# KlokWave_Wave.net
KiCad netlist of a schematic drawn in Altium Designer
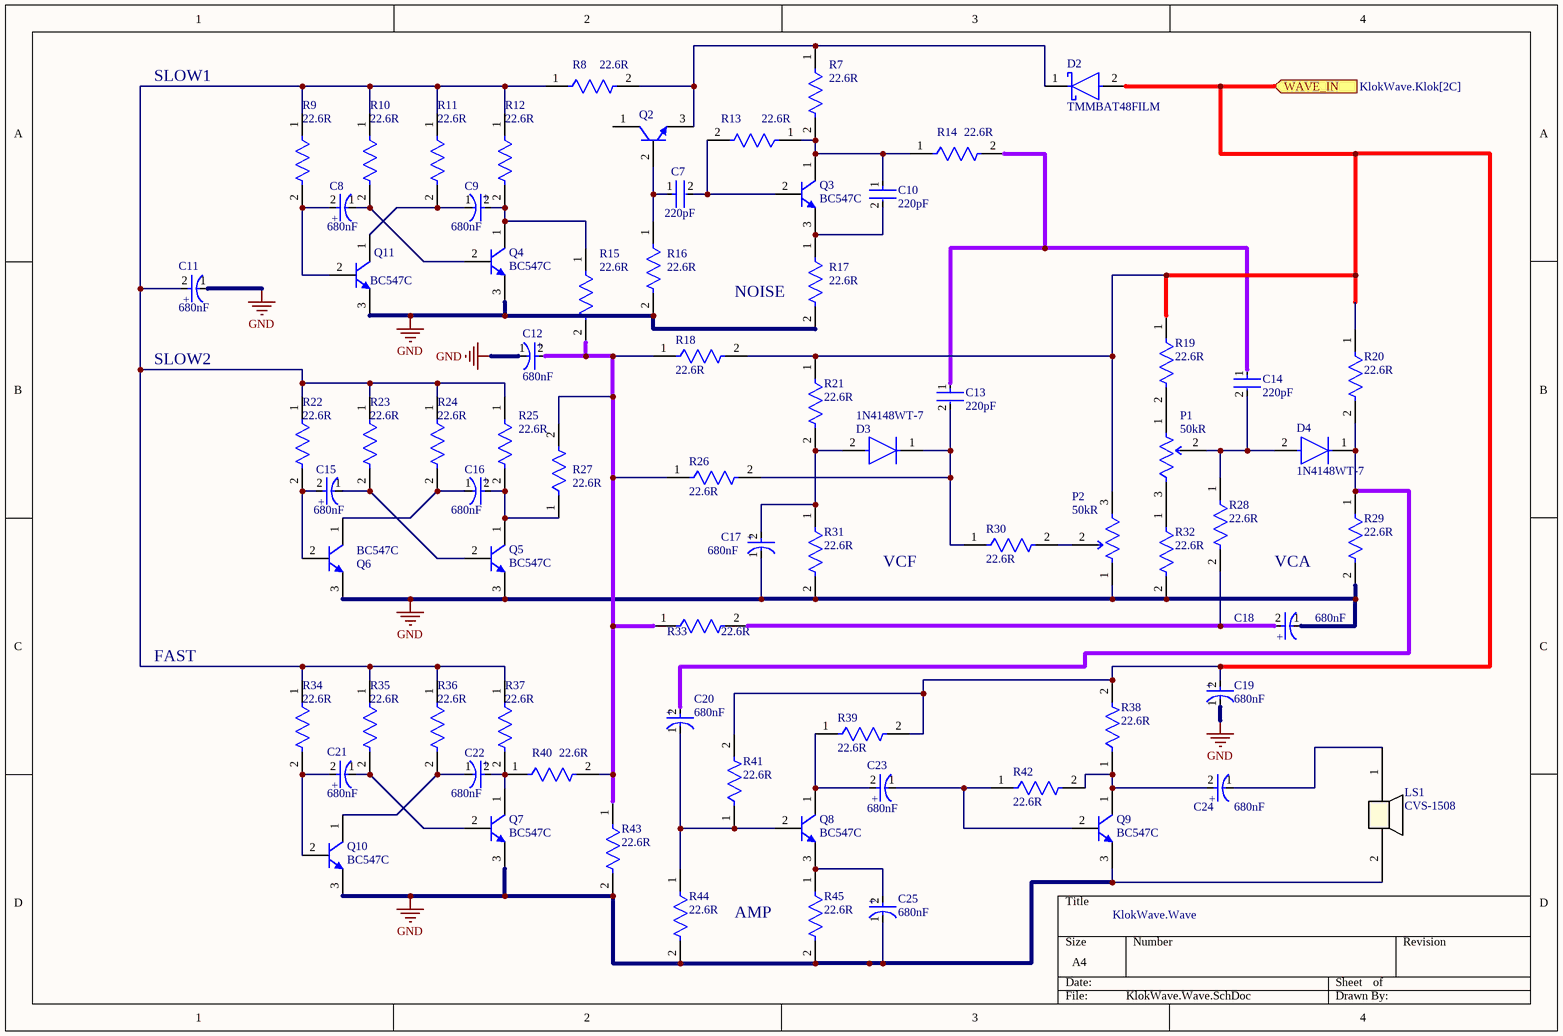
[diagram p0: KlokWave.Wave.SchDoc]

(export (version "E")
  (design (tool "Eeschema 10.0.6"))
  (components
    (comp (ref "C7")
      (value "CL21C221FBANNNC")
      (footprint "SMD RES: 0805ph")
      (description "SMD cap nonpol: CL21 Series 0805 220pF 50V ±1% Tolerance C0G Multilayer Ceramic Chip Capacitor")
      (fields (field (name "TOLERANCE") "1%") (field (name "CAPACITANCE") "220pF"))
      (libsource (lib "KlokWave") (part "CMP-13271-000769-1"))
    )
    (comp (ref "C8")
      (value "FP-OS-CON-SMT-C6-MFG")
      (footprint "SMD Elco pol: FP-OS-CON-SMT-C6-MFG")
      (description "SMD Elco Capacitor")
      (fields (field (name "CAPACITANCE") "680nF") (field (name "TOLERANCE") "10%"))
      (libsource (lib "KlokWave") (part "FP-OS-CON-SMT-C6-MFG"))
    )
    (comp (ref "C9")
      (value "FP-OS-CON-SMT-C6-MFG")
      (footprint "SMD Elco pol: FP-OS-CON-SMT-C6-MFG")
      (description "SMD Elco Capacitor")
      (fields (field (name "CAPACITANCE") "680nF") (field (name "TOLERANCE") "10%"))
      (libsource (lib "KlokWave") (part "FP-OS-CON-SMT-C6-MFG"))
    )
    (comp (ref "C10")
      (value "CL21C221FBANNNC")
      (footprint "SMD RES: 0805ph")
      (description "SMD cap nonpol: CL21 Series 0805 220pF 50V ±1% Tolerance C0G Multilayer Ceramic Chip Capacitor")
      (fields (field (name "TOLERANCE") "1%") (field (name "CAPACITANCE") "220pF"))
      (libsource (lib "KlokWave") (part "CMP-13271-000769-1"))
    )
    (comp (ref "C11")
      (value "FP-OS-CON-SMT-C6-MFG")
      (footprint "SMD Elco pol: FP-OS-CON-SMT-C6-MFG")
      (description "SMD Elco Capacitor")
      (fields (field (name "CAPACITANCE") "680nF") (field (name "TOLERANCE") "10%"))
      (libsource (lib "KlokWave") (part "FP-OS-CON-SMT-C6-MFG"))
    )
    (comp (ref "C12")
      (value "FP-OS-CON-SMT-C6-MFG")
      (footprint "SMD Elco pol: FP-OS-CON-SMT-C6-MFG")
      (description "SMD Elco Capacitor")
      (fields (field (name "CAPACITANCE") "680nF") (field (name "TOLERANCE") "10%"))
      (libsource (lib "KlokWave") (part "FP-OS-CON-SMT-C6-MFG"))
    )
    (comp (ref "C13")
      (value "CL21C221FBANNNC")
      (footprint "SMD RES: 0805ph")
      (description "SMD cap nonpol: CL21 Series 0805 220pF 50V ±1% Tolerance C0G Multilayer Ceramic Chip Capacitor")
      (fields (field (name "TOLERANCE") "1%") (field (name "CAPACITANCE") "220pF"))
      (libsource (lib "KlokWave") (part "CMP-13271-000769-1"))
    )
    (comp (ref "C14")
      (value "CL21C221FBANNNC")
      (footprint "SMD RES: 0805ph")
      (description "SMD cap nonpol: CL21 Series 0805 220pF 50V ±1% Tolerance C0G Multilayer Ceramic Chip Capacitor")
      (fields (field (name "TOLERANCE") "1%") (field (name "CAPACITANCE") "220pF"))
      (libsource (lib "KlokWave") (part "CMP-13271-000769-1"))
    )
    (comp (ref "C15")
      (value "FP-OS-CON-SMT-C6-MFG")
      (footprint "SMD Elco pol: FP-OS-CON-SMT-C6-MFG")
      (description "SMD Elco Capacitor")
      (fields (field (name "CAPACITANCE") "680nF") (field (name "TOLERANCE") "10%"))
      (libsource (lib "KlokWave") (part "FP-OS-CON-SMT-C6-MFG"))
    )
    (comp (ref "C16")
      (value "FP-OS-CON-SMT-C6-MFG")
      (footprint "SMD Elco pol: FP-OS-CON-SMT-C6-MFG")
      (description "SMD Elco Capacitor")
      (fields (field (name "CAPACITANCE") "680nF") (field (name "TOLERANCE") "10%"))
      (libsource (lib "KlokWave") (part "FP-OS-CON-SMT-C6-MFG"))
    )
    (comp (ref "C17")
      (value "FP-OS-CON-SMT-C6-MFG")
      (footprint "SMD Elco pol: FP-OS-CON-SMT-C6-MFG")
      (description "SMD Elco Capacitor")
      (fields (field (name "CAPACITANCE") "680nF") (field (name "TOLERANCE") "10%"))
      (libsource (lib "KlokWave") (part "FP-OS-CON-SMT-C6-MFG"))
    )
    (comp (ref "C18")
      (value "FP-OS-CON-SMT-C6-MFG")
      (footprint "SMD Elco pol: FP-OS-CON-SMT-C6-MFG")
      (description "SMD Elco Capacitor")
      (fields (field (name "CAPACITANCE") "680nF") (field (name "TOLERANCE") "10%"))
      (libsource (lib "KlokWave") (part "FP-OS-CON-SMT-C6-MFG"))
    )
    (comp (ref "C19")
      (value "FP-OS-CON-SMT-C6-MFG")
      (footprint "SMD Elco pol: FP-OS-CON-SMT-C6-MFG")
      (description "SMD Elco Capacitor")
      (fields (field (name "CAPACITANCE") "680nF") (field (name "TOLERANCE") "10%"))
      (libsource (lib "KlokWave") (part "FP-OS-CON-SMT-C6-MFG"))
    )
    (comp (ref "C20")
      (value "FP-OS-CON-SMT-C6-MFG")
      (footprint "SMD Elco pol: FP-OS-CON-SMT-C6-MFG")
      (description "SMD Elco Capacitor")
      (fields (field (name "CAPACITANCE") "680nF") (field (name "TOLERANCE") "10%"))
      (libsource (lib "KlokWave") (part "FP-OS-CON-SMT-C6-MFG"))
    )
    (comp (ref "C21")
      (value "FP-OS-CON-SMT-C6-MFG")
      (footprint "SMD Elco pol: FP-OS-CON-SMT-C6-MFG")
      (description "SMD Elco Capacitor")
      (fields (field (name "CAPACITANCE") "680nF") (field (name "TOLERANCE") "10%"))
      (libsource (lib "KlokWave") (part "FP-OS-CON-SMT-C6-MFG"))
    )
    (comp (ref "C22")
      (value "FP-OS-CON-SMT-C6-MFG")
      (footprint "SMD Elco pol: FP-OS-CON-SMT-C6-MFG")
      (description "SMD Elco Capacitor")
      (fields (field (name "CAPACITANCE") "680nF") (field (name "TOLERANCE") "10%"))
      (libsource (lib "KlokWave") (part "FP-OS-CON-SMT-C6-MFG"))
    )
    (comp (ref "C23")
      (value "FP-OS-CON-SMT-C6-MFG")
      (footprint "SMD Elco pol: FP-OS-CON-SMT-C6-MFG")
      (description "SMD Elco Capacitor")
      (fields (field (name "CAPACITANCE") "680nF") (field (name "TOLERANCE") "10%"))
      (libsource (lib "KlokWave") (part "FP-OS-CON-SMT-C6-MFG"))
    )
    (comp (ref "C24")
      (value "FP-OS-CON-SMT-C6-MFG")
      (footprint "SMD Elco pol: FP-OS-CON-SMT-C6-MFG")
      (description "SMD Elco Capacitor")
      (fields (field (name "CAPACITANCE") "680nF") (field (name "TOLERANCE") "10%"))
      (libsource (lib "KlokWave") (part "FP-OS-CON-SMT-C6-MFG"))
    )
    (comp (ref "C25")
      (value "FP-OS-CON-SMT-C6-MFG")
      (footprint "SMD Elco pol: FP-OS-CON-SMT-C6-MFG")
      (description "SMD Elco Capacitor")
      (fields (field (name "CAPACITANCE") "680nF") (field (name "TOLERANCE") "10%"))
      (libsource (lib "KlokWave") (part "FP-OS-CON-SMT-C6-MFG"))
    )
    (comp (ref "D2")
      (value "TMMBAT48FILM")
      (footprint "SMD Diode BAT48 FP-MINIMELF-MFG")
      (description "Rectifier Diode BAT48 SCHOTTKY 40V 350MA MINMELF")
      (fields
        (field (name "MANUFACTURER") "STMicroelectronics")
        (field (name "OCTOPART") "https://octopart.com/tmmbat48film-stmicroelectronics-324396")
      )
      (libsource (lib "KlokWave") (part "CMP-12187-000003-1"))
    )
    (comp (ref "D3")
      (value "1N4148WT-7")
      (footprint "SMD Diode Rect: FP-SOD523-MFG")
      (description "Rectifier Diode 1N4148 GEN PURP 80V 125MA SOD523")
      (libsource (lib "KlokWave") (part "CMP-2000-05518-3"))
    )
    (comp (ref "D4")
      (value "1N4148WT-7")
      (footprint "SMD Diode Rect: FP-SOD523-MFG")
      (description "Rectifier Diode 1N4148 GEN PURP 80V 125MA SOD523")
      (libsource (lib "KlokWave") (part "CMP-2000-05518-3"))
    )
    (comp (ref "LS1")
      (value "CVS-1508")
      (footprint "THT speaker: CVS-1508_CUD")
      (description "THT Speaker")
      (libsource (lib "KlokWave") (part "CVS-1508"))
    )
    (comp (ref "P1")
      (value "3361P-1-503GLF")
      (footprint "SMD POT: FP-3361P-MFG")
      (description "SMD TRIMMER 50K OHM 0.5W GW TOP ADJ")
      (fields (field (name "TOLERANCE") "10%") (field (name "RESISTANCE") "50kR"))
      (libsource (lib "KlokWave") (part "CMP-07234-000057-1"))
    )
    (comp (ref "P2")
      (value "3361P-1-503GLF")
      (footprint "SMD POT: FP-3361P-MFG")
      (description "SMD TRIMMER 50K OHM 0.5W GW TOP ADJ")
      (fields (field (name "TOLERANCE") "10%") (field (name "RESISTANCE") "50kR"))
      (libsource (lib "KlokWave") (part "CMP-07234-000057-1"))
    )
    (comp (ref "Q2")
      (value "BC547C")
      (footprint "THT NPN Transistor: ONSC-TO-92-3-29-11_AM_BL")
      (description "BC547C: THT Amplifier Transistor, NPN Silicon, 3-Pin TO-92, Bulk Box")
      (fields (field (name "MANUFACTURER") "On Semiconductor"))
      (libsource (lib "KlokWave") (part "CMP-1048-01437-1"))
    )
    (comp (ref "Q3")
      (value "BC547C")
      (footprint "THT NPN Transistor: ONSC-TO-92-3-29-11_AM_BL")
      (description "BC547C: THT Amplifier Transistor, NPN Silicon, 3-Pin TO-92, Bulk Box")
      (fields (field (name "MANUFACTURER") "On Semiconductor"))
      (libsource (lib "KlokWave") (part "CMP-1048-01437-1"))
    )
    (comp (ref "Q4")
      (value "BC547C")
      (footprint "THT NPN Transistor: ONSC-TO-92-3-29-11_AM_BL")
      (description "BC547C: THT Amplifier Transistor, NPN Silicon, 3-Pin TO-92, Bulk Box")
      (fields (field (name "MANUFACTURER") "On Semiconductor"))
      (libsource (lib "KlokWave") (part "CMP-1048-01437-1"))
    )
    (comp (ref "Q5")
      (value "BC547C")
      (footprint "THT NPN Transistor: ONSC-TO-92-3-29-11_AM_BL")
      (description "BC547C: THT Amplifier Transistor, NPN Silicon, 3-Pin TO-92, Bulk Box")
      (fields (field (name "MANUFACTURER") "On Semiconductor"))
      (libsource (lib "KlokWave") (part "CMP-1048-01437-1"))
    )
    (comp (ref "Q6")
      (value "BC547C")
      (footprint "THT NPN Transistor: ONSC-TO-92-3-29-11_AM_BL")
      (description "BC547C: THT Amplifier Transistor, NPN Silicon, 3-Pin TO-92, Bulk Box")
      (fields (field (name "MANUFACTURER") "On Semiconductor"))
      (libsource (lib "KlokWave") (part "CMP-1048-01437-1"))
    )
    (comp (ref "Q7")
      (value "BC547C")
      (footprint "THT NPN Transistor: ONSC-TO-92-3-29-11_AM_BL")
      (description "BC547C: THT Amplifier Transistor, NPN Silicon, 3-Pin TO-92, Bulk Box")
      (fields (field (name "MANUFACTURER") "On Semiconductor"))
      (libsource (lib "KlokWave") (part "CMP-1048-01437-1"))
    )
    (comp (ref "Q8")
      (value "BC547C")
      (footprint "THT NPN Transistor: ONSC-TO-92-3-29-11_AM_BL")
      (description "BC547C: THT Amplifier Transistor, NPN Silicon, 3-Pin TO-92, Bulk Box")
      (fields (field (name "MANUFACTURER") "On Semiconductor"))
      (libsource (lib "KlokWave") (part "CMP-1048-01437-1"))
    )
    (comp (ref "Q9")
      (value "BC547C")
      (footprint "THT NPN Transistor: ONSC-TO-92-3-29-11_AM_BL")
      (description "BC547C: THT Amplifier Transistor, NPN Silicon, 3-Pin TO-92, Bulk Box")
      (fields (field (name "MANUFACTURER") "On Semiconductor"))
      (libsource (lib "KlokWave") (part "CMP-1048-01437-1"))
    )
    (comp (ref "Q10")
      (value "BC547C")
      (footprint "THT NPN Transistor: ONSC-TO-92-3-29-11_AM_BL")
      (description "BC547C: THT Amplifier Transistor, NPN Silicon, 3-Pin TO-92, Bulk Box")
      (fields (field (name "MANUFACTURER") "On Semiconductor"))
      (libsource (lib "KlokWave") (part "CMP-1048-01437-1"))
    )
    (comp (ref "Q11")
      (value "BC547C")
      (footprint "THT NPN Transistor: ONSC-TO-92-3-29-11_AM_BL")
      (description "BC547C: THT Amplifier Transistor, NPN Silicon, 3-Pin TO-92, Bulk Box")
      (fields (field (name "MANUFACTURER") "On Semiconductor"))
      (libsource (lib "KlokWave") (part "CMP-1048-01437-1"))
    )
    (comp (ref "R7")
      (value "CR0805-FX-22R6ELF")
      (footprint "SMD RES: 0805ph")
      (description "Thick Film Chip Resistors 0805 22.6Ω 0.125W 1% 100ppm/°C")
      (fields (field (name "TOLERANCE") "1%") (field (name "RESISTANCE") "22.6R"))
      (libsource (lib "KlokWave") (part "CMP-07231-006076-1"))
    )
    (comp (ref "R8")
      (value "CR0805-FX-22R6ELF")
      (footprint "SMD RES: 0805ph")
      (description "Thick Film Chip Resistors 0805 22.6Ω 0.125W 1% 100ppm/°C")
      (fields (field (name "TOLERANCE") "1%") (field (name "RESISTANCE") "22.6R"))
      (libsource (lib "KlokWave") (part "CMP-07231-006076-1"))
    )
    (comp (ref "R9")
      (value "CR0805-FX-22R6ELF")
      (footprint "SMD RES: 0805ph")
      (description "Thick Film Chip Resistors 0805 22.6Ω 0.125W 1% 100ppm/°C")
      (fields (field (name "TOLERANCE") "1%") (field (name "RESISTANCE") "22.6R"))
      (libsource (lib "KlokWave") (part "CMP-07231-006076-1"))
    )
    (comp (ref "R10")
      (value "CR0805-FX-22R6ELF")
      (footprint "SMD RES: 0805ph")
      (description "Thick Film Chip Resistors 0805 22.6Ω 0.125W 1% 100ppm/°C")
      (fields (field (name "TOLERANCE") "1%") (field (name "RESISTANCE") "22.6R"))
      (libsource (lib "KlokWave") (part "CMP-07231-006076-1"))
    )
    (comp (ref "R11")
      (value "CR0805-FX-22R6ELF")
      (footprint "SMD RES: 0805ph")
      (description "Thick Film Chip Resistors 0805 22.6Ω 0.125W 1% 100ppm/°C")
      (fields (field (name "TOLERANCE") "1%") (field (name "RESISTANCE") "22.6R"))
      (libsource (lib "KlokWave") (part "CMP-07231-006076-1"))
    )
    (comp (ref "R12")
      (value "CR0805-FX-22R6ELF")
      (footprint "SMD RES: 0805ph")
      (description "Thick Film Chip Resistors 0805 22.6Ω 0.125W 1% 100ppm/°C")
      (fields (field (name "TOLERANCE") "1%") (field (name "RESISTANCE") "22.6R"))
      (libsource (lib "KlokWave") (part "CMP-07231-006076-1"))
    )
    (comp (ref "R13")
      (value "CR0805-FX-22R6ELF")
      (footprint "SMD RES: 0805ph")
      (description "Thick Film Chip Resistors 0805 22.6Ω 0.125W 1% 100ppm/°C")
      (fields (field (name "TOLERANCE") "1%") (field (name "RESISTANCE") "22.6R"))
      (libsource (lib "KlokWave") (part "CMP-07231-006076-1"))
    )
    (comp (ref "R14")
      (value "CR0805-FX-22R6ELF")
      (footprint "SMD RES: 0805ph")
      (description "Thick Film Chip Resistors 0805 22.6Ω 0.125W 1% 100ppm/°C")
      (fields (field (name "TOLERANCE") "1%") (field (name "RESISTANCE") "22.6R"))
      (libsource (lib "KlokWave") (part "CMP-07231-006076-1"))
    )
    (comp (ref "R15")
      (value "CR0805-FX-22R6ELF")
      (footprint "SMD RES: 0805ph")
      (description "Thick Film Chip Resistors 0805 22.6Ω 0.125W 1% 100ppm/°C")
      (fields (field (name "TOLERANCE") "1%") (field (name "RESISTANCE") "22.6R"))
      (libsource (lib "KlokWave") (part "CMP-07231-006076-1"))
    )
    (comp (ref "R16")
      (value "CR0805-FX-22R6ELF")
      (footprint "SMD RES: 0805ph")
      (description "Thick Film Chip Resistors 0805 22.6Ω 0.125W 1% 100ppm/°C")
      (fields (field (name "TOLERANCE") "1%") (field (name "RESISTANCE") "22.6R"))
      (libsource (lib "KlokWave") (part "CMP-07231-006076-1"))
    )
    (comp (ref "R17")
      (value "CR0805-FX-22R6ELF")
      (footprint "SMD RES: 0805ph")
      (description "Thick Film Chip Resistors 0805 22.6Ω 0.125W 1% 100ppm/°C")
      (fields (field (name "TOLERANCE") "1%") (field (name "RESISTANCE") "22.6R"))
      (libsource (lib "KlokWave") (part "CMP-07231-006076-1"))
    )
    (comp (ref "R18")
      (value "CR0805-FX-22R6ELF")
      (footprint "SMD RES: 0805ph")
      (description "Thick Film Chip Resistors 0805 22.6Ω 0.125W 1% 100ppm/°C")
      (fields (field (name "TOLERANCE") "1%") (field (name "RESISTANCE") "22.6R"))
      (libsource (lib "KlokWave") (part "CMP-07231-006076-1"))
    )
    (comp (ref "R19")
      (value "CR0805-FX-22R6ELF")
      (footprint "SMD RES: 0805ph")
      (description "Thick Film Chip Resistors 0805 22.6Ω 0.125W 1% 100ppm/°C")
      (fields (field (name "TOLERANCE") "1%") (field (name "RESISTANCE") "22.6R"))
      (libsource (lib "KlokWave") (part "CMP-07231-006076-1"))
    )
    (comp (ref "R20")
      (value "CR0805-FX-22R6ELF")
      (footprint "SMD RES: 0805ph")
      (description "Thick Film Chip Resistors 0805 22.6Ω 0.125W 1% 100ppm/°C")
      (fields (field (name "TOLERANCE") "1%") (field (name "RESISTANCE") "22.6R"))
      (libsource (lib "KlokWave") (part "CMP-07231-006076-1"))
    )
    (comp (ref "R21")
      (value "CR0805-FX-22R6ELF")
      (footprint "SMD RES: 0805ph")
      (description "Thick Film Chip Resistors 0805 22.6Ω 0.125W 1% 100ppm/°C")
      (fields (field (name "TOLERANCE") "1%") (field (name "RESISTANCE") "22.6R"))
      (libsource (lib "KlokWave") (part "CMP-07231-006076-1"))
    )
    (comp (ref "R22")
      (value "CR0805-FX-22R6ELF")
      (footprint "SMD RES: 0805ph")
      (description "Thick Film Chip Resistors 0805 22.6Ω 0.125W 1% 100ppm/°C")
      (fields (field (name "TOLERANCE") "1%") (field (name "RESISTANCE") "22.6R"))
      (libsource (lib "KlokWave") (part "CMP-07231-006076-1"))
    )
    (comp (ref "R23")
      (value "CR0805-FX-22R6ELF")
      (footprint "SMD RES: 0805ph")
      (description "Thick Film Chip Resistors 0805 22.6Ω 0.125W 1% 100ppm/°C")
      (fields (field (name "TOLERANCE") "1%") (field (name "RESISTANCE") "22.6R"))
      (libsource (lib "KlokWave") (part "CMP-07231-006076-1"))
    )
    (comp (ref "R24")
      (value "CR0805-FX-22R6ELF")
      (footprint "SMD RES: 0805ph")
      (description "Thick Film Chip Resistors 0805 22.6Ω 0.125W 1% 100ppm/°C")
      (fields (field (name "TOLERANCE") "1%") (field (name "RESISTANCE") "22.6R"))
      (libsource (lib "KlokWave") (part "CMP-07231-006076-1"))
    )
    (comp (ref "R25")
      (value "CR0805-FX-22R6ELF")
      (footprint "SMD RES: 0805ph")
      (description "Thick Film Chip Resistors 0805 22.6Ω 0.125W 1% 100ppm/°C")
      (fields (field (name "TOLERANCE") "1%") (field (name "RESISTANCE") "22.6R"))
      (libsource (lib "KlokWave") (part "CMP-07231-006076-1"))
    )
    (comp (ref "R26")
      (value "CR0805-FX-22R6ELF")
      (footprint "SMD RES: 0805ph")
      (description "Thick Film Chip Resistors 0805 22.6Ω 0.125W 1% 100ppm/°C")
      (fields (field (name "TOLERANCE") "1%") (field (name "RESISTANCE") "22.6R"))
      (libsource (lib "KlokWave") (part "CMP-07231-006076-1"))
    )
    (comp (ref "R27")
      (value "CR0805-FX-22R6ELF")
      (footprint "SMD RES: 0805ph")
      (description "Thick Film Chip Resistors 0805 22.6Ω 0.125W 1% 100ppm/°C")
      (fields (field (name "TOLERANCE") "1%") (field (name "RESISTANCE") "22.6R"))
      (libsource (lib "KlokWave") (part "CMP-07231-006076-1"))
    )
    (comp (ref "R28")
      (value "CR0805-FX-22R6ELF")
      (footprint "SMD RES: 0805ph")
      (description "Thick Film Chip Resistors 0805 22.6Ω 0.125W 1% 100ppm/°C")
      (fields (field (name "TOLERANCE") "1%") (field (name "RESISTANCE") "22.6R"))
      (libsource (lib "KlokWave") (part "CMP-07231-006076-1"))
    )
    (comp (ref "R29")
      (value "CR0805-FX-22R6ELF")
      (footprint "SMD RES: 0805ph")
      (description "Thick Film Chip Resistors 0805 22.6Ω 0.125W 1% 100ppm/°C")
      (fields (field (name "TOLERANCE") "1%") (field (name "RESISTANCE") "22.6R"))
      (libsource (lib "KlokWave") (part "CMP-07231-006076-1"))
    )
    (comp (ref "R30")
      (value "CR0805-FX-22R6ELF")
      (footprint "SMD RES: 0805ph")
      (description "Thick Film Chip Resistors 0805 22.6Ω 0.125W 1% 100ppm/°C")
      (fields (field (name "TOLERANCE") "1%") (field (name "RESISTANCE") "22.6R"))
      (libsource (lib "KlokWave") (part "CMP-07231-006076-1"))
    )
    (comp (ref "R31")
      (value "CR0805-FX-22R6ELF")
      (footprint "SMD RES: 0805ph")
      (description "Thick Film Chip Resistors 0805 22.6Ω 0.125W 1% 100ppm/°C")
      (fields (field (name "TOLERANCE") "1%") (field (name "RESISTANCE") "22.6R"))
      (libsource (lib "KlokWave") (part "CMP-07231-006076-1"))
    )
    (comp (ref "R32")
      (value "CR0805-FX-22R6ELF")
      (footprint "SMD RES: 0805ph")
      (description "Thick Film Chip Resistors 0805 22.6Ω 0.125W 1% 100ppm/°C")
      (fields (field (name "TOLERANCE") "1%") (field (name "RESISTANCE") "22.6R"))
      (libsource (lib "KlokWave") (part "CMP-07231-006076-1"))
    )
    (comp (ref "R33")
      (value "CR0805-FX-22R6ELF")
      (footprint "SMD RES: 0805ph")
      (description "Thick Film Chip Resistors 0805 22.6Ω 0.125W 1% 100ppm/°C")
      (fields (field (name "TOLERANCE") "1%") (field (name "RESISTANCE") "22.6R"))
      (libsource (lib "KlokWave") (part "CMP-07231-006076-1"))
    )
    (comp (ref "R34")
      (value "CR0805-FX-22R6ELF")
      (footprint "SMD RES: 0805ph")
      (description "Thick Film Chip Resistors 0805 22.6Ω 0.125W 1% 100ppm/°C")
      (fields (field (name "TOLERANCE") "1%") (field (name "RESISTANCE") "22.6R"))
      (libsource (lib "KlokWave") (part "CMP-07231-006076-1"))
    )
    (comp (ref "R35")
      (value "CR0805-FX-22R6ELF")
      (footprint "SMD RES: 0805ph")
      (description "Thick Film Chip Resistors 0805 22.6Ω 0.125W 1% 100ppm/°C")
      (fields (field (name "TOLERANCE") "1%") (field (name "RESISTANCE") "22.6R"))
      (libsource (lib "KlokWave") (part "CMP-07231-006076-1"))
    )
    (comp (ref "R36")
      (value "CR0805-FX-22R6ELF")
      (footprint "SMD RES: 0805ph")
      (description "Thick Film Chip Resistors 0805 22.6Ω 0.125W 1% 100ppm/°C")
      (fields (field (name "TOLERANCE") "1%") (field (name "RESISTANCE") "22.6R"))
      (libsource (lib "KlokWave") (part "CMP-07231-006076-1"))
    )
    (comp (ref "R37")
      (value "CR0805-FX-22R6ELF")
      (footprint "SMD RES: 0805ph")
      (description "Thick Film Chip Resistors 0805 22.6Ω 0.125W 1% 100ppm/°C")
      (fields (field (name "TOLERANCE") "1%") (field (name "RESISTANCE") "22.6R"))
      (libsource (lib "KlokWave") (part "CMP-07231-006076-1"))
    )
    (comp (ref "R38")
      (value "CR0805-FX-22R6ELF")
      (footprint "SMD RES: 0805ph")
      (description "Thick Film Chip Resistors 0805 22.6Ω 0.125W 1% 100ppm/°C")
      (fields (field (name "TOLERANCE") "1%") (field (name "RESISTANCE") "22.6R"))
      (libsource (lib "KlokWave") (part "CMP-07231-006076-1"))
    )
    (comp (ref "R39")
      (value "CR0805-FX-22R6ELF")
      (footprint "SMD RES: 0805ph")
      (description "Thick Film Chip Resistors 0805 22.6Ω 0.125W 1% 100ppm/°C")
      (fields (field (name "TOLERANCE") "1%") (field (name "RESISTANCE") "22.6R"))
      (libsource (lib "KlokWave") (part "CMP-07231-006076-1"))
    )
    (comp (ref "R40")
      (value "CR0805-FX-22R6ELF")
      (footprint "SMD RES: 0805ph")
      (description "Thick Film Chip Resistors 0805 22.6Ω 0.125W 1% 100ppm/°C")
      (fields (field (name "TOLERANCE") "1%") (field (name "RESISTANCE") "22.6R"))
      (libsource (lib "KlokWave") (part "CMP-07231-006076-1"))
    )
    (comp (ref "R41")
      (value "CR0805-FX-22R6ELF")
      (footprint "SMD RES: 0805ph")
      (description "Thick Film Chip Resistors 0805 22.6Ω 0.125W 1% 100ppm/°C")
      (fields (field (name "TOLERANCE") "1%") (field (name "RESISTANCE") "22.6R"))
      (libsource (lib "KlokWave") (part "CMP-07231-006076-1"))
    )
    (comp (ref "R42")
      (value "CR0805-FX-22R6ELF")
      (footprint "SMD RES: 0805ph")
      (description "Thick Film Chip Resistors 0805 22.6Ω 0.125W 1% 100ppm/°C")
      (fields (field (name "TOLERANCE") "1%") (field (name "RESISTANCE") "22.6R"))
      (libsource (lib "KlokWave") (part "CMP-07231-006076-1"))
    )
    (comp (ref "R43")
      (value "CR0805-FX-22R6ELF")
      (footprint "SMD RES: 0805ph")
      (description "Thick Film Chip Resistors 0805 22.6Ω 0.125W 1% 100ppm/°C")
      (fields (field (name "TOLERANCE") "1%") (field (name "RESISTANCE") "22.6R"))
      (libsource (lib "KlokWave") (part "CMP-07231-006076-1"))
    )
    (comp (ref "R44")
      (value "CR0805-FX-22R6ELF")
      (footprint "SMD RES: 0805ph")
      (description "Thick Film Chip Resistors 0805 22.6Ω 0.125W 1% 100ppm/°C")
      (fields (field (name "TOLERANCE") "1%") (field (name "RESISTANCE") "22.6R"))
      (libsource (lib "KlokWave") (part "CMP-07231-006076-1"))
    )
    (comp (ref "R45")
      (value "CR0805-FX-22R6ELF")
      (footprint "SMD RES: 0805ph")
      (description "Thick Film Chip Resistors 0805 22.6Ω 0.125W 1% 100ppm/°C")
      (fields (field (name "TOLERANCE") "1%") (field (name "RESISTANCE") "22.6R"))
      (libsource (lib "KlokWave") (part "CMP-07231-006076-1"))
    )
  )
  (nets
    (net (code "1") (name "/WAVE_IN") (class "Default")
      (node (ref "C19") (pin "2") (pinfunction "A_2") (pintype "passive"))
      (node (ref "D2") (pin "2") (pinfunction "A_2") (pintype "passive"))
      (node (ref "P2") (pin "3") (pinfunction "CW_3") (pintype "passive"))
      (node (ref "R18") (pin "2") (pinfunction "2_2") (pintype "passive"))
      (node (ref "R19") (pin "1") (pinfunction "1_1") (pintype "passive"))
      (node (ref "R20") (pin "1") (pinfunction "1_1") (pintype "passive"))
      (node (ref "R21") (pin "1") (pinfunction "1_1") (pintype "passive"))
      (node (ref "R38") (pin "2") (pinfunction "2_2") (pintype "passive"))
      (node (ref "R39") (pin "2") (pinfunction "2_2") (pintype "passive"))
      (node (ref "R41") (pin "2") (pinfunction "2_2") (pintype "passive"))
    )
    (net (code "2") (name "GND") (class "Default")
      (node (ref "C11") (pin "1") (pinfunction "C_1") (pintype "passive"))
      (node (ref "C12") (pin "1") (pinfunction "C_1") (pintype "passive"))
      (node (ref "C17") (pin "1") (pinfunction "C_1") (pintype "passive"))
      (node (ref "C18") (pin "1") (pinfunction "C_1") (pintype "passive"))
      (node (ref "C19") (pin "1") (pinfunction "C_1") (pintype "passive"))
      (node (ref "C25") (pin "1") (pinfunction "C_1") (pintype "passive"))
      (node (ref "LS1") (pin "2") (pinfunction "2_2") (pintype "passive"))
      (node (ref "P2") (pin "1") (pinfunction "CCW_1") (pintype "passive"))
      (node (ref "Q10") (pin "3") (pinfunction "E_3") (pintype "passive"))
      (node (ref "Q11") (pin "3") (pinfunction "E_3") (pintype "passive"))
      (node (ref "Q4") (pin "3") (pinfunction "E_3") (pintype "passive"))
      (node (ref "Q5") (pin "3") (pinfunction "E_3") (pintype "passive"))
      (node (ref "Q6") (pin "3") (pinfunction "E_3") (pintype "passive"))
      (node (ref "Q7") (pin "3") (pinfunction "E_3") (pintype "passive"))
      (node (ref "Q9") (pin "3") (pinfunction "E_3") (pintype "passive"))
      (node (ref "R16") (pin "2") (pinfunction "2_2") (pintype "passive"))
      (node (ref "R17") (pin "2") (pinfunction "2_2") (pintype "passive"))
      (node (ref "R29") (pin "2") (pinfunction "2_2") (pintype "passive"))
      (node (ref "R31") (pin "2") (pinfunction "2_2") (pintype "passive"))
      (node (ref "R32") (pin "2") (pinfunction "2_2") (pintype "passive"))
      (node (ref "R43") (pin "2") (pinfunction "2_2") (pintype "passive"))
      (node (ref "R44") (pin "2") (pinfunction "2_2") (pintype "passive"))
      (node (ref "R45") (pin "2") (pinfunction "2_2") (pintype "passive"))
    )
    (net (code "3") (name "Net-(C8-A)") (class "Default")
      (node (ref "C8") (pin "2") (pinfunction "A_2") (pintype "passive"))
      (node (ref "Q11") (pin "2") (pinfunction "B_2") (pintype "passive"))
      (node (ref "R9") (pin "2") (pinfunction "2_2") (pintype "passive"))
    )
    (net (code "4") (name "Net-(C8-C)") (class "Default")
      (node (ref "C8") (pin "1") (pinfunction "C_1") (pintype "passive"))
      (node (ref "Q4") (pin "2") (pinfunction "B_2") (pintype "passive"))
      (node (ref "R10") (pin "2") (pinfunction "2_2") (pintype "passive"))
    )
    (net (code "5") (name "Net-(C9-A)") (class "Default")
      (node (ref "C9") (pin "2") (pinfunction "A_2") (pintype "passive"))
      (node (ref "Q4") (pin "1") (pinfunction "C_1") (pintype "passive"))
      (node (ref "R12") (pin "2") (pinfunction "2_2") (pintype "passive"))
      (node (ref "R15") (pin "1") (pinfunction "1_1") (pintype "passive"))
    )
    (net (code "6") (name "Net-(C9-C)") (class "Default")
      (node (ref "C9") (pin "1") (pinfunction "C_1") (pintype "passive"))
      (node (ref "Q11") (pin "1") (pinfunction "C_1") (pintype "passive"))
      (node (ref "R11") (pin "2") (pinfunction "2_2") (pintype "passive"))
    )
    (net (code "7") (name "Net-(C11-A)") (class "Default")
      (node (ref "C11") (pin "2") (pinfunction "A_2") (pintype "passive"))
      (node (ref "R10") (pin "1") (pinfunction "1_1") (pintype "passive"))
      (node (ref "R11") (pin "1") (pinfunction "1_1") (pintype "passive"))
      (node (ref "R12") (pin "1") (pinfunction "1_1") (pintype "passive"))
      (node (ref "R22") (pin "1") (pinfunction "1_1") (pintype "passive"))
      (node (ref "R23") (pin "1") (pinfunction "1_1") (pintype "passive"))
      (node (ref "R24") (pin "1") (pinfunction "1_1") (pintype "passive"))
      (node (ref "R25") (pin "1") (pinfunction "1_1") (pintype "passive"))
      (node (ref "R34") (pin "1") (pinfunction "1_1") (pintype "passive"))
      (node (ref "R35") (pin "1") (pinfunction "1_1") (pintype "passive"))
      (node (ref "R36") (pin "1") (pinfunction "1_1") (pintype "passive"))
      (node (ref "R37") (pin "1") (pinfunction "1_1") (pintype "passive"))
      (node (ref "R8") (pin "1") (pinfunction "1_1") (pintype "passive"))
      (node (ref "R9") (pin "1") (pinfunction "1_1") (pintype "passive"))
    )
    (net (code "8") (name "Net-(C12-A)") (class "Default")
      (node (ref "C12") (pin "2") (pinfunction "A_2") (pintype "passive"))
      (node (ref "R15") (pin "2") (pinfunction "2_2") (pintype "passive"))
      (node (ref "R18") (pin "1") (pinfunction "1_1") (pintype "passive"))
      (node (ref "R26") (pin "1") (pinfunction "1_1") (pintype "passive"))
      (node (ref "R27") (pin "2") (pinfunction "2_2") (pintype "passive"))
      (node (ref "R33") (pin "1") (pinfunction "1_1") (pintype "passive"))
      (node (ref "R40") (pin "2") (pinfunction "2_2") (pintype "passive"))
      (node (ref "R43") (pin "1") (pinfunction "1_1") (pintype "passive"))
    )
    (net (code "9") (name "Net-(C13-Pad1)") (class "Default")
      (node (ref "C13") (pin "1") (pinfunction "1_1") (pintype "passive"))
      (node (ref "C14") (pin "1") (pinfunction "1_1") (pintype "passive"))
      (node (ref "R14") (pin "2") (pinfunction "2_2") (pintype "passive"))
    )
    (net (code "10") (name "Net-(C15-A)") (class "Default")
      (node (ref "C15") (pin "2") (pinfunction "A_2") (pintype "passive"))
      (node (ref "Q6") (pin "2") (pinfunction "B_2") (pintype "passive"))
      (node (ref "R22") (pin "2") (pinfunction "2_2") (pintype "passive"))
    )
    (net (code "11") (name "Net-(C15-C)") (class "Default")
      (node (ref "C15") (pin "1") (pinfunction "C_1") (pintype "passive"))
      (node (ref "Q5") (pin "2") (pinfunction "B_2") (pintype "passive"))
      (node (ref "R23") (pin "2") (pinfunction "2_2") (pintype "passive"))
    )
    (net (code "12") (name "Net-(C16-A)") (class "Default")
      (node (ref "C16") (pin "2") (pinfunction "A_2") (pintype "passive"))
      (node (ref "Q5") (pin "1") (pinfunction "C_1") (pintype "passive"))
      (node (ref "R25") (pin "2") (pinfunction "2_2") (pintype "passive"))
      (node (ref "R27") (pin "1") (pinfunction "1_1") (pintype "passive"))
    )
    (net (code "13") (name "Net-(C16-C)") (class "Default")
      (node (ref "C16") (pin "1") (pinfunction "C_1") (pintype "passive"))
      (node (ref "Q6") (pin "1") (pinfunction "C_1") (pintype "passive"))
      (node (ref "R24") (pin "2") (pinfunction "2_2") (pintype "passive"))
    )
    (net (code "14") (name "Net-(C17-A)") (class "Default")
      (node (ref "C17") (pin "2") (pinfunction "A_2") (pintype "passive"))
      (node (ref "D3") (pin "2") (pinfunction "A_2") (pintype "passive"))
      (node (ref "R21") (pin "2") (pinfunction "2_2") (pintype "passive"))
      (node (ref "R31") (pin "1") (pinfunction "1_1") (pintype "passive"))
    )
    (net (code "15") (name "Net-(C18-A)") (class "Default")
      (node (ref "C18") (pin "2") (pinfunction "A_2") (pintype "passive"))
      (node (ref "R28") (pin "2") (pinfunction "2_2") (pintype "passive"))
      (node (ref "R33") (pin "2") (pinfunction "2_2") (pintype "passive"))
    )
    (net (code "16") (name "Net-(C20-A)") (class "Default")
      (node (ref "C20") (pin "2") (pinfunction "A_2") (pintype "passive"))
      (node (ref "D4") (pin "1") (pinfunction "C_1") (pintype "passive"))
      (node (ref "R20") (pin "2") (pinfunction "2_2") (pintype "passive"))
      (node (ref "R29") (pin "1") (pinfunction "1_1") (pintype "passive"))
    )
    (net (code "17") (name "Net-(C20-C)") (class "Default")
      (node (ref "C20") (pin "1") (pinfunction "C_1") (pintype "passive"))
      (node (ref "Q8") (pin "2") (pinfunction "B_2") (pintype "passive"))
      (node (ref "R41") (pin "1") (pinfunction "1_1") (pintype "passive"))
      (node (ref "R44") (pin "1") (pinfunction "1_1") (pintype "passive"))
    )
    (net (code "18") (name "Net-(C21-A)") (class "Default")
      (node (ref "C21") (pin "2") (pinfunction "A_2") (pintype "passive"))
      (node (ref "Q10") (pin "2") (pinfunction "B_2") (pintype "passive"))
      (node (ref "R34") (pin "2") (pinfunction "2_2") (pintype "passive"))
    )
    (net (code "19") (name "Net-(C21-C)") (class "Default")
      (node (ref "C21") (pin "1") (pinfunction "C_1") (pintype "passive"))
      (node (ref "Q7") (pin "2") (pinfunction "B_2") (pintype "passive"))
      (node (ref "R35") (pin "2") (pinfunction "2_2") (pintype "passive"))
    )
    (net (code "20") (name "Net-(C22-A)") (class "Default")
      (node (ref "C22") (pin "2") (pinfunction "A_2") (pintype "passive"))
      (node (ref "Q7") (pin "1") (pinfunction "C_1") (pintype "passive"))
      (node (ref "R37") (pin "2") (pinfunction "2_2") (pintype "passive"))
      (node (ref "R40") (pin "1") (pinfunction "1_1") (pintype "passive"))
    )
    (net (code "21") (name "Net-(C22-C)") (class "Default")
      (node (ref "C22") (pin "1") (pinfunction "C_1") (pintype "passive"))
      (node (ref "Q10") (pin "1") (pinfunction "C_1") (pintype "passive"))
      (node (ref "R36") (pin "2") (pinfunction "2_2") (pintype "passive"))
    )
    (net (code "22") (name "Net-(C23-A)") (class "Default")
      (node (ref "C23") (pin "2") (pinfunction "A_2") (pintype "passive"))
      (node (ref "Q8") (pin "1") (pinfunction "C_1") (pintype "passive"))
      (node (ref "R39") (pin "1") (pinfunction "1_1") (pintype "passive"))
    )
    (net (code "23") (name "Net-(C23-C)") (class "Default")
      (node (ref "C23") (pin "1") (pinfunction "C_1") (pintype "passive"))
      (node (ref "Q9") (pin "2") (pinfunction "B_2") (pintype "passive"))
      (node (ref "R42") (pin "1") (pinfunction "1_1") (pintype "passive"))
    )
    (net (code "24") (name "Net-(C24-A)") (class "Default")
      (node (ref "C24") (pin "2") (pinfunction "A_2") (pintype "passive"))
      (node (ref "Q9") (pin "1") (pinfunction "C_1") (pintype "passive"))
      (node (ref "R38") (pin "1") (pinfunction "1_1") (pintype "passive"))
      (node (ref "R42") (pin "2") (pinfunction "2_2") (pintype "passive"))
    )
    (net (code "25") (name "Net-(C24-C)") (class "Default")
      (node (ref "C24") (pin "1") (pinfunction "C_1") (pintype "passive"))
      (node (ref "LS1") (pin "1") (pinfunction "1_1") (pintype "passive"))
    )
    (net (code "26") (name "Net-(C25-A)") (class "Default")
      (node (ref "C25") (pin "2") (pinfunction "A_2") (pintype "passive"))
      (node (ref "Q8") (pin "3") (pinfunction "E_3") (pintype "passive"))
      (node (ref "R45") (pin "1") (pinfunction "1_1") (pintype "passive"))
    )
    (net (code "27") (name "Net-(D2-C)") (class "Default")
      (node (ref "D2") (pin "1") (pinfunction "C_1") (pintype "passive"))
      (node (ref "Q2") (pin "3") (pinfunction "E_3") (pintype "passive"))
      (node (ref "R7") (pin "1") (pinfunction "1_1") (pintype "passive"))
      (node (ref "R8") (pin "2") (pinfunction "2_2") (pintype "passive"))
    )
    (net (code "28") (name "Net-(D3-C)") (class "Default")
      (node (ref "C13") (pin "2") (pinfunction "2_2") (pintype "passive"))
      (node (ref "D3") (pin "1") (pinfunction "C_1") (pintype "passive"))
      (node (ref "R26") (pin "2") (pinfunction "2_2") (pintype "passive"))
      (node (ref "R30") (pin "1") (pinfunction "1_1") (pintype "passive"))
    )
    (net (code "29") (name "Net-(D4-A)") (class "Default")
      (node (ref "C14") (pin "2") (pinfunction "2_2") (pintype "passive"))
      (node (ref "D4") (pin "2") (pinfunction "A_2") (pintype "passive"))
      (node (ref "P1") (pin "2") (pinfunction "WIPER_2") (pintype "passive"))
      (node (ref "R28") (pin "1") (pinfunction "1_1") (pintype "passive"))
    )
    (net (code "30") (name "Net-(P1-CCW)") (class "Default")
      (node (ref "P1") (pin "1") (pinfunction "CCW_1") (pintype "passive"))
      (node (ref "R19") (pin "2") (pinfunction "2_2") (pintype "passive"))
    )
    (net (code "31") (name "Net-(P1-CW)") (class "Default")
      (node (ref "P1") (pin "3") (pinfunction "CW_3") (pintype "passive"))
      (node (ref "R32") (pin "1") (pinfunction "1_1") (pintype "passive"))
    )
    (net (code "32") (name "Net-(P2-WIPER)") (class "Default")
      (node (ref "P2") (pin "2") (pinfunction "WIPER_2") (pintype "passive"))
      (node (ref "R30") (pin "2") (pinfunction "2_2") (pintype "passive"))
    )
    (net (code "33") (name "Net-(Q2-B)") (class "Default")
      (node (ref "C7") (pin "1") (pinfunction "1_1") (pintype "passive"))
      (node (ref "Q2") (pin "2") (pinfunction "B_2") (pintype "passive"))
      (node (ref "R16") (pin "1") (pinfunction "1_1") (pintype "passive"))
    )
    (net (code "34") (name "Net-(Q3-B)") (class "Default")
      (node (ref "C7") (pin "2") (pinfunction "2_2") (pintype "passive"))
      (node (ref "Q3") (pin "2") (pinfunction "B_2") (pintype "passive"))
      (node (ref "R13") (pin "2") (pinfunction "2_2") (pintype "passive"))
    )
    (net (code "35") (name "Net-(Q3-C)") (class "Default")
      (node (ref "C10") (pin "1") (pinfunction "1_1") (pintype "passive"))
      (node (ref "Q3") (pin "1") (pinfunction "C_1") (pintype "passive"))
      (node (ref "R13") (pin "1") (pinfunction "1_1") (pintype "passive"))
      (node (ref "R14") (pin "1") (pinfunction "1_1") (pintype "passive"))
      (node (ref "R7") (pin "2") (pinfunction "2_2") (pintype "passive"))
    )
    (net (code "36") (name "Net-(Q3-E)") (class "Default")
      (node (ref "C10") (pin "2") (pinfunction "2_2") (pintype "passive"))
      (node (ref "Q3") (pin "3") (pinfunction "E_3") (pintype "passive"))
      (node (ref "R17") (pin "1") (pinfunction "1_1") (pintype "passive"))
    )
    (net (code "37") (name "unconnected-(Q2-C-Pad1)") (class "Default")
      (node (ref "Q2") (pin "1") (pinfunction "C_1") (pintype "passive"))
    )
  )
)
